# GrooveCard.net
KiCad netlist of a schematic drawn in EAGLE
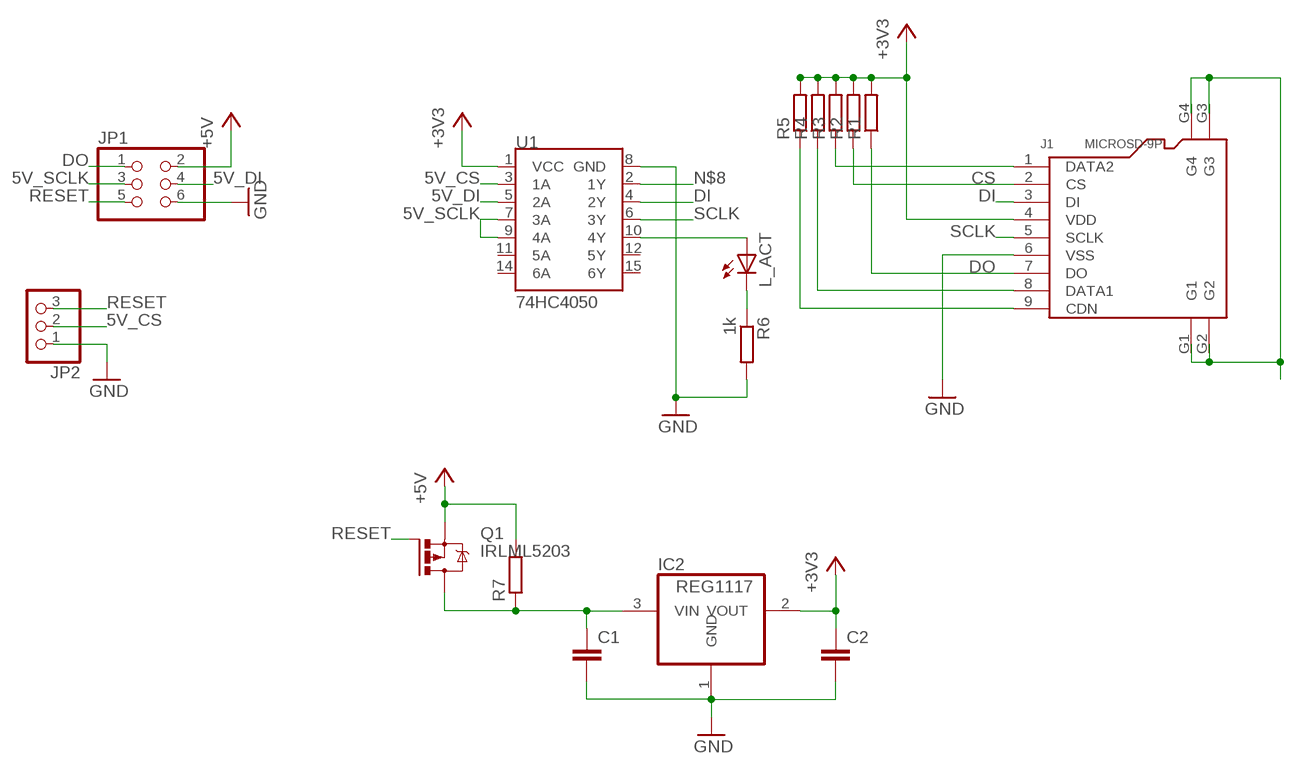
[diagram p0: schematic, sheet 1]

(export (version "E")
  (design (tool "Eeschema 10.0.6"))
  (components
    (comp (ref "C1")
      (value "C-EUC0805")
      (footprint "eagle-import:C0805")
      (libsource (lib "eagle-import") (part "C-EUC0805"))
    )
    (comp (ref "C2")
      (value "C-EUC0805")
      (footprint "eagle-import:C0805")
      (libsource (lib "eagle-import") (part "C-EUC0805"))
    )
    (comp (ref "IC2")
      (value "REG1117")
      (footprint "eagle-import:SOT223")
      (libsource (lib "eagle-import") (part "REG1117"))
    )
    (comp (ref "J1")
      (value "MICROSD-9P")
      (footprint "eagle-import:MICRO-SD9+4P-SMD-16.1X14.5X1.85MM")
      (libsource (lib "eagle-import") (part "MICRO-SD-CARD-HOLDER-9P"))
    )
    (comp (ref "JP1")
      (value "PINHD-2X3")
      (footprint "eagle-import:2X03")
      (libsource (lib "eagle-import") (part "PINHD-2X3"))
    )
    (comp (ref "JP2")
      (value "PINHD-1X3")
      (footprint "eagle-import:1X03")
      (libsource (lib "eagle-import") (part "PINHD-1X3"))
    )
    (comp (ref "L_ACT")
      (value "LEDCHIPLED_0805")
      (footprint "eagle-import:CHIPLED_0805")
      (libsource (lib "eagle-import") (part "LEDCHIPLED_0805"))
    )
    (comp (ref "Q1")
      (value "IRLML5203")
      (footprint "eagle-import:MICRO3")
      (libsource (lib "eagle-import") (part "IRLML5203"))
    )
    (comp (ref "R1")
      (value "R-EU_M0805")
      (footprint "eagle-import:M0805")
      (libsource (lib "eagle-import") (part "R-EU_M0805"))
    )
    (comp (ref "R2")
      (value "R-EU_M0805")
      (footprint "eagle-import:M0805")
      (libsource (lib "eagle-import") (part "R-EU_M0805"))
    )
    (comp (ref "R3")
      (value "R-EU_M0805")
      (footprint "eagle-import:M0805")
      (libsource (lib "eagle-import") (part "R-EU_M0805"))
    )
    (comp (ref "R4")
      (value "R-EU_M0805")
      (footprint "eagle-import:M0805")
      (libsource (lib "eagle-import") (part "R-EU_M0805"))
    )
    (comp (ref "R5")
      (value "R-EU_M0805")
      (footprint "eagle-import:M0805")
      (libsource (lib "eagle-import") (part "R-EU_M0805"))
    )
    (comp (ref "R6")
      (value "1k")
      (footprint "eagle-import:M0805")
      (libsource (lib "eagle-import") (part "R-EU_M0805"))
    )
    (comp (ref "R7")
      (value "R-EU_R0805")
      (footprint "eagle-import:R0805")
      (libsource (lib "eagle-import") (part "R-EU_R0805"))
    )
    (comp (ref "U1")
      (value "74HC4050")
      (footprint "eagle-import:SO16")
      (libsource (lib "eagle-import") (part "HEX_CONVERTER"))
    )
  )
  (nets
    (net (code "1") (name "+3V3") (class "Default")
      (node (ref "C2") (pin "1") (pinfunction "1_1") (pintype "passive"))
      (node (ref "IC2") (pin "2") (pinfunction "VOUT_2") (pintype "output"))
      (node (ref "J1") (pin "4") (pinfunction "VDD_4") (pintype "bidirectional"))
      (node (ref "R1") (pin "2") (pinfunction "2_2") (pintype "passive"))
      (node (ref "R2") (pin "2") (pinfunction "2_2") (pintype "passive"))
      (node (ref "R3") (pin "2") (pinfunction "2_2") (pintype "passive"))
      (node (ref "R4") (pin "2") (pinfunction "2_2") (pintype "passive"))
      (node (ref "R5") (pin "2") (pinfunction "2_2") (pintype "passive"))
      (node (ref "U1") (pin "1") (pinfunction "VCC_1") (pintype "bidirectional"))
    )
    (net (code "2") (name "+5V") (class "Default")
      (node (ref "JP1") (pin "2") (pinfunction "2_2") (pintype "passive"))
      (node (ref "Q1") (pin "2") (pinfunction "S_2") (pintype "passive"))
      (node (ref "R7") (pin "2") (pinfunction "2_2") (pintype "passive"))
    )
    (net (code "3") (name "/5V_CS") (class "Default")
      (node (ref "JP2") (pin "2") (pinfunction "2_2") (pintype "passive"))
      (node (ref "U1") (pin "3") (pinfunction "1A_3") (pintype "bidirectional"))
    )
    (net (code "4") (name "/5V_DI") (class "Default")
      (node (ref "JP1") (pin "4") (pinfunction "4_4") (pintype "passive"))
      (node (ref "U1") (pin "5") (pinfunction "2A_5") (pintype "bidirectional"))
    )
    (net (code "5") (name "/5V_SCLK") (class "Default")
      (node (ref "JP1") (pin "3") (pinfunction "3_3") (pintype "passive"))
      (node (ref "U1") (pin "7") (pinfunction "3A_7") (pintype "bidirectional"))
      (node (ref "U1") (pin "9") (pinfunction "4A_9") (pintype "bidirectional"))
    )
    (net (code "6") (name "/CS") (class "Default")
      (node (ref "J1") (pin "2") (pinfunction "CS_2") (pintype "bidirectional"))
      (node (ref "R2") (pin "1") (pinfunction "1_1") (pintype "passive"))
    )
    (net (code "7") (name "/DI") (class "Default")
      (node (ref "J1") (pin "3") (pinfunction "DI_3") (pintype "bidirectional"))
      (node (ref "U1") (pin "4") (pinfunction "2Y_4") (pintype "bidirectional"))
    )
    (net (code "8") (name "/DO") (class "Default")
      (node (ref "J1") (pin "7") (pinfunction "DO_7") (pintype "bidirectional"))
      (node (ref "JP1") (pin "1") (pinfunction "1_1") (pintype "passive"))
      (node (ref "R1") (pin "1") (pinfunction "1_1") (pintype "passive"))
    )
    (net (code "9") (name "/N$8") (class "Default")
      (node (ref "U1") (pin "2") (pinfunction "1Y_2") (pintype "bidirectional"))
    )
    (net (code "10") (name "/RESET") (class "Default")
      (node (ref "JP1") (pin "5") (pinfunction "5_5") (pintype "passive"))
      (node (ref "JP2") (pin "3") (pinfunction "3_3") (pintype "passive"))
      (node (ref "Q1") (pin "1") (pinfunction "G_1") (pintype "passive"))
    )
    (net (code "11") (name "/SCLK") (class "Default")
      (node (ref "J1") (pin "5") (pinfunction "SCLK_5") (pintype "bidirectional"))
      (node (ref "U1") (pin "6") (pinfunction "3Y_6") (pintype "bidirectional"))
    )
    (net (code "12") (name "GND") (class "Default")
      (node (ref "C1") (pin "2") (pinfunction "2_2") (pintype "passive"))
      (node (ref "C2") (pin "2") (pinfunction "2_2") (pintype "passive"))
      (node (ref "IC2") (pin "1") (pinfunction "GND_1") (pintype "power_in"))
      (node (ref "J1") (pin "6") (pinfunction "VSS_6") (pintype "bidirectional"))
      (node (ref "JP1") (pin "6") (pinfunction "6_6") (pintype "passive"))
      (node (ref "JP2") (pin "1") (pinfunction "1_1") (pintype "passive"))
      (node (ref "R6") (pin "2") (pinfunction "2_2") (pintype "passive"))
      (node (ref "U1") (pin "8") (pinfunction "GND_8") (pintype "bidirectional"))
    )
    (net (code "13") (name "Net-(IC2-VIN)") (class "Default")
      (node (ref "C1") (pin "1") (pinfunction "1_1") (pintype "passive"))
      (node (ref "IC2") (pin "3") (pinfunction "VIN_3") (pintype "input"))
      (node (ref "Q1") (pin "3") (pinfunction "D_3") (pintype "passive"))
      (node (ref "R7") (pin "1") (pinfunction "1_1") (pintype "passive"))
    )
    (net (code "14") (name "Net-(J1-CDN)") (class "Default")
      (node (ref "J1") (pin "9") (pinfunction "CDN_9") (pintype "bidirectional"))
      (node (ref "R5") (pin "1") (pinfunction "1_1") (pintype "passive"))
    )
    (net (code "15") (name "Net-(J1-DATA1)") (class "Default")
      (node (ref "J1") (pin "8") (pinfunction "DATA1_8") (pintype "bidirectional"))
      (node (ref "R4") (pin "1") (pinfunction "1_1") (pintype "passive"))
    )
    (net (code "16") (name "Net-(J1-DATA2)") (class "Default")
      (node (ref "J1") (pin "1") (pinfunction "DATA2_1") (pintype "bidirectional"))
      (node (ref "R3") (pin "1") (pinfunction "1_1") (pintype "passive"))
    )
    (net (code "17") (name "Net-(L_ACT-PadC)") (class "Default")
      (node (ref "L_ACT") (pin "C") (pinfunction "C_C") (pintype "passive"))
      (node (ref "R6") (pin "1") (pinfunction "1_1") (pintype "passive"))
    )
    (net (code "18") (name "Net-(U1-4Y)") (class "Default")
      (node (ref "L_ACT") (pin "A") (pinfunction "A_A") (pintype "passive"))
      (node (ref "U1") (pin "10") (pinfunction "4Y_10") (pintype "bidirectional"))
    )
    (net (code "19") (name "unconnected-(J1-PadG1)") (class "Default")
      (node (ref "J1") (pin "G1") (pinfunction "G1_G1") (pintype "bidirectional"))
    )
    (net (code "20") (name "unconnected-(J1-PadG2)") (class "Default")
      (node (ref "J1") (pin "G2") (pinfunction "G2_G2") (pintype "bidirectional"))
    )
    (net (code "21") (name "unconnected-(J1-PadG3)") (class "Default")
      (node (ref "J1") (pin "G3") (pinfunction "G3_G3") (pintype "bidirectional"))
    )
    (net (code "22") (name "unconnected-(J1-PadG4)") (class "Default")
      (node (ref "J1") (pin "G4") (pinfunction "G4_G4") (pintype "bidirectional"))
    )
    (net (code "23") (name "unconnected-(U1-5A-Pad11)") (class "Default")
      (node (ref "U1") (pin "11") (pinfunction "5A_11") (pintype "bidirectional"))
    )
    (net (code "24") (name "unconnected-(U1-5Y-Pad12)") (class "Default")
      (node (ref "U1") (pin "12") (pinfunction "5Y_12") (pintype "bidirectional"))
    )
    (net (code "25") (name "unconnected-(U1-6A-Pad14)") (class "Default")
      (node (ref "U1") (pin "14") (pinfunction "6A_14") (pintype "bidirectional"))
    )
    (net (code "26") (name "unconnected-(U1-6Y-Pad15)") (class "Default")
      (node (ref "U1") (pin "15") (pinfunction "6Y_15") (pintype "bidirectional"))
    )
  )
)
